# SAM_E54_Xplained_Pro_current_measurement.net
KiCad netlist of a schematic drawn in Altium Designer
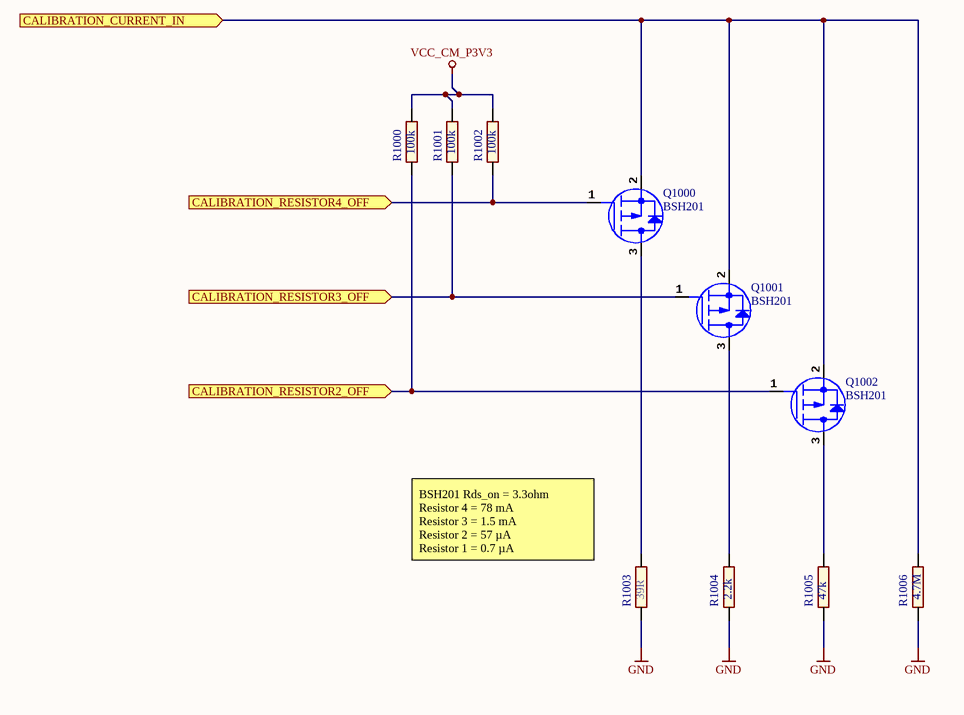
[diagram p0: SAM_E54_Xplained_Pro_current_measurement_calibration.SchDoc]

(export (version "E")
  (design (tool "Eeschema 10.0.6"))
  (components
    (comp (ref "Q1000")
      (value "BSH201")
      (footprint "AP5-00002")
      (fields (field (name "MANUFACTURER") "NXP") (field (name "MPN") "BSH201,215"))
      (libsource (lib "AltiumDbLib") (part "MOSFET_P_GSD"))
    )
    (comp (ref "Q1001")
      (value "BSH201")
      (footprint "AP5-00002")
      (fields (field (name "MANUFACTURER") "NXP") (field (name "MPN") "BSH201,215"))
      (libsource (lib "AltiumDbLib") (part "MOSFET_P_GSD"))
    )
    (comp (ref "Q1002")
      (value "BSH201")
      (footprint "AP5-00002")
      (fields (field (name "MANUFACTURER") "NXP") (field (name "MPN") "BSH201,215"))
      (libsource (lib "AltiumDbLib") (part "MOSFET_P_GSD"))
    )
    (comp (ref "R1000")
      (value "100k")
      (footprint "AP2-00011")
      (description "Thick film resistor, SMD 0402, 1/16W, 1%")
      (fields (field (name "TOLERANCE") "1 %") (field (name "MANUFACTURER") "ASJ"))
      (libsource (lib "AltiumDbLib") (part "R2"))
    )
    (comp (ref "R1001")
      (value "100k")
      (footprint "AP2-00011")
      (description "Thick film resistor, SMD 0402, 1/16W, 1%")
      (fields (field (name "TOLERANCE") "1 %") (field (name "MANUFACTURER") "ASJ"))
      (libsource (lib "AltiumDbLib") (part "R2"))
    )
    (comp (ref "R1002")
      (value "100k")
      (footprint "AP2-00011")
      (description "Thick film resistor, SMD 0402, 1/16W, 1%")
      (fields (field (name "TOLERANCE") "1 %") (field (name "MANUFACTURER") "ASJ"))
      (libsource (lib "AltiumDbLib") (part "R2"))
    )
    (comp (ref "R1003")
      (value "39R")
      (footprint "AP2-00011")
      (description "Thick film resistor, SMD 0402, 1/16W, 1%")
      (fields (field (name "TOLERANCE") "1 %") (field (name "MANUFACTURER") "ASJ"))
      (libsource (lib "AltiumDbLib") (part "R2"))
    )
    (comp (ref "R1004")
      (value "2.2k")
      (footprint "AP2-00011")
      (description "Thick film resistor, SMD 0402, 1/16W, 1%")
      (fields (field (name "TOLERANCE") "1 %") (field (name "MANUFACTURER") "ASJ"))
      (libsource (lib "AltiumDbLib") (part "R2"))
    )
    (comp (ref "R1005")
      (value "47k")
      (footprint "AP2-00011")
      (description "Thick film resistor, SMD 0402, 1/16W, 1%")
      (fields (field (name "TOLERANCE") "1 %") (field (name "MANUFACTURER") "KOA"))
      (libsource (lib "AltiumDbLib") (part "R2"))
    )
    (comp (ref "R1006")
      (value "4.7M")
      (footprint "AP2-00011")
      (description "Thick film SMD 0402 1/16W 1%")
      (fields (field (name "TOLERANCE") "1 %") (field (name "MANUFACTURER") "YAGEO CORP"))
      (libsource (lib "AltiumDbLib") (part "R2"))
    )
  )
  (nets
    (net (code "1") (name "/CALIBRATION_CURRENT_IN") (class "Default")
      (node (ref "Q1000") (pin "2") (pinfunction "S_2") (pintype "passive"))
      (node (ref "Q1001") (pin "2") (pinfunction "S_2") (pintype "passive"))
      (node (ref "Q1002") (pin "2") (pinfunction "S_2") (pintype "passive"))
      (node (ref "R1006") (pin "2") (pinfunction "2_2") (pintype "passive"))
    )
    (net (code "2") (name "/CALIBRATION_RESISTOR2_OFF") (class "Default")
      (node (ref "Q1002") (pin "1") (pinfunction "G_1") (pintype "passive"))
      (node (ref "R1000") (pin "1") (pinfunction "1_1") (pintype "passive"))
    )
    (net (code "3") (name "/CALIBRATION_RESISTOR3_OFF") (class "Default")
      (node (ref "Q1001") (pin "1") (pinfunction "G_1") (pintype "passive"))
      (node (ref "R1001") (pin "1") (pinfunction "1_1") (pintype "passive"))
    )
    (net (code "4") (name "/CALIBRATION_RESISTOR4_OFF") (class "Default")
      (node (ref "Q1000") (pin "1") (pinfunction "G_1") (pintype "passive"))
      (node (ref "R1002") (pin "1") (pinfunction "1_1") (pintype "passive"))
    )
    (net (code "5") (name "GND") (class "Default")
      (node (ref "R1003") (pin "1") (pinfunction "1_1") (pintype "passive"))
      (node (ref "R1004") (pin "1") (pinfunction "1_1") (pintype "passive"))
      (node (ref "R1005") (pin "1") (pinfunction "1_1") (pintype "passive"))
      (node (ref "R1006") (pin "1") (pinfunction "1_1") (pintype "passive"))
    )
    (net (code "6") (name "Net-(Q1000-D)") (class "Default")
      (node (ref "Q1000") (pin "3") (pinfunction "D_3") (pintype "passive"))
      (node (ref "R1003") (pin "2") (pinfunction "2_2") (pintype "passive"))
    )
    (net (code "7") (name "Net-(Q1001-D)") (class "Default")
      (node (ref "Q1001") (pin "3") (pinfunction "D_3") (pintype "passive"))
      (node (ref "R1004") (pin "2") (pinfunction "2_2") (pintype "passive"))
    )
    (net (code "8") (name "Net-(Q1002-D)") (class "Default")
      (node (ref "Q1002") (pin "3") (pinfunction "D_3") (pintype "passive"))
      (node (ref "R1005") (pin "2") (pinfunction "2_2") (pintype "passive"))
    )
    (net (code "9") (name "VCC_CM_P3V3") (class "Default")
      (node (ref "R1000") (pin "2") (pinfunction "2_2") (pintype "passive"))
      (node (ref "R1001") (pin "2") (pinfunction "2_2") (pintype "passive"))
      (node (ref "R1002") (pin "2") (pinfunction "2_2") (pintype "passive"))
    )
  )
)
